# ThermoDisplay.net
KiCad netlist of a schematic drawn in Altium Designer
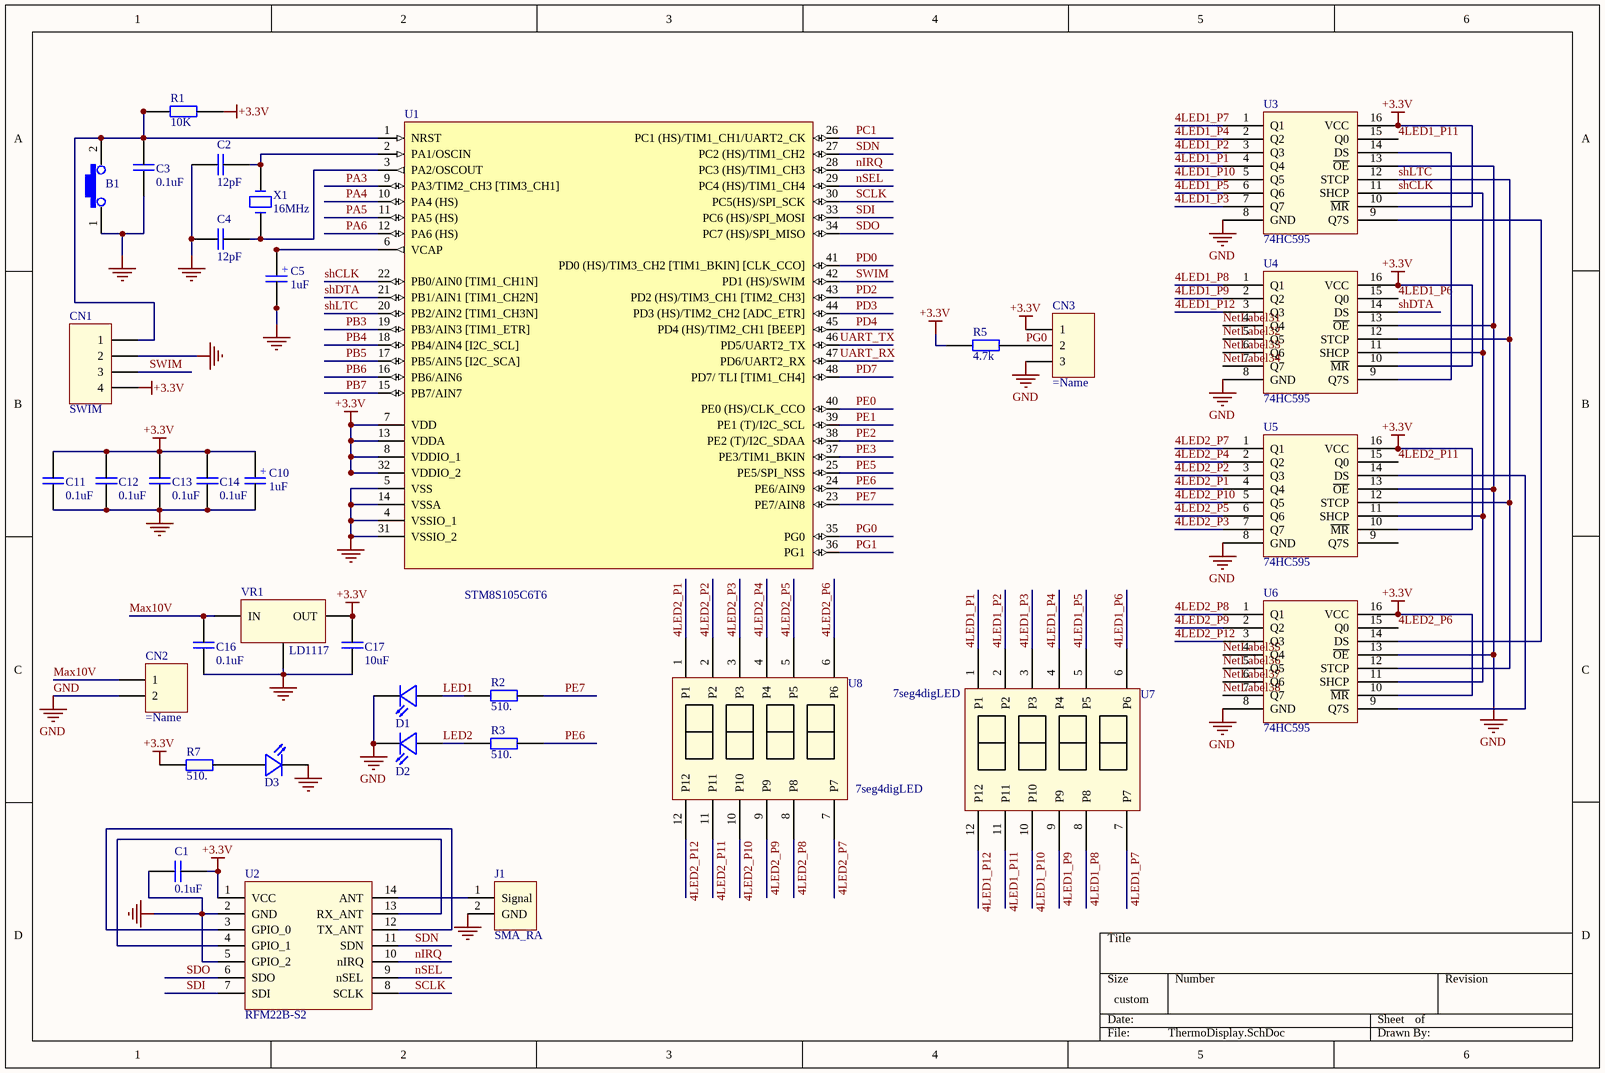
[diagram p0: ThermoDisplay.SchDoc]

(export (version "E")
  (design (tool "Eeschema 10.0.6"))
  (components
    (comp (ref "B1")
      (value "~")
      (footprint "FSMSM")
      (description "Button")
      (fields (field (name "PART NUMBER") "FSM14JRT"))
      (libsource (lib "Library") (part "Button"))
    )
    (comp (ref "C1")
      (value "0.1uF")
      (footprint "Cap0805")
      (description "Capacitor")
      (fields (field (name "PART NUMBER") "Cap 0805 0.1uF") (field (name "TOLERANCE") "±5%"))
      (libsource (lib "Library") (part "Capacitor"))
    )
    (comp (ref "C2")
      (value "12pF")
      (footprint "Cap0805")
      (description "Capacitor")
      (fields (field (name "PART NUMBER") "Cap 0805 12pF") (field (name "TOLERANCE") "±5%"))
      (libsource (lib "Library") (part "Capacitor"))
    )
    (comp (ref "C3")
      (value "0.1uF")
      (footprint "Cap0805")
      (description "Capacitor")
      (fields (field (name "PART NUMBER") "Cap 0805 0.1uF") (field (name "TOLERANCE") "±5%"))
      (libsource (lib "Library") (part "Capacitor"))
    )
    (comp (ref "C4")
      (value "12pF")
      (footprint "Cap0805")
      (description "Capacitor")
      (fields (field (name "PART NUMBER") "Cap 0805 12pF") (field (name "TOLERANCE") "±5%"))
      (libsource (lib "Library") (part "Capacitor"))
    )
    (comp (ref "C5")
      (value "1uF")
      (footprint "TC_A")
      (description "Capacitor polarity")
      (fields (field (name "PART NUMBER") "TCap TC_A 1uF") (field (name "VOLTAGE") "25V"))
      (libsource (lib "Library") (part "Capacitor polarity"))
    )
    (comp (ref "C10")
      (value "1uF")
      (footprint "TC_A")
      (description "Capacitor polarity")
      (fields (field (name "PART NUMBER") "TCap TC_A 1uF") (field (name "VOLTAGE") "25V"))
      (libsource (lib "Library") (part "Capacitor polarity"))
    )
    (comp (ref "C11")
      (value "0.1uF")
      (footprint "Cap0805")
      (description "Capacitor")
      (fields (field (name "PART NUMBER") "Cap 0805 0.1uF") (field (name "TOLERANCE") "±5%"))
      (libsource (lib "Library") (part "Capacitor"))
    )
    (comp (ref "C12")
      (value "0.1uF")
      (footprint "Cap0805")
      (description "Capacitor")
      (fields (field (name "PART NUMBER") "Cap 0805 0.1uF") (field (name "TOLERANCE") "±5%"))
      (libsource (lib "Library") (part "Capacitor"))
    )
    (comp (ref "C13")
      (value "0.1uF")
      (footprint "Cap0805")
      (description "Capacitor")
      (fields (field (name "PART NUMBER") "Cap 0805 0.1uF") (field (name "TOLERANCE") "±5%"))
      (libsource (lib "Library") (part "Capacitor"))
    )
    (comp (ref "C14")
      (value "0.1uF")
      (footprint "Cap0805")
      (description "Capacitor")
      (fields (field (name "PART NUMBER") "Cap 0805 0.1uF") (field (name "TOLERANCE") "±5%"))
      (libsource (lib "Library") (part "Capacitor"))
    )
    (comp (ref "C16")
      (value "0.1uF")
      (footprint "Cap0805")
      (description "Capacitor")
      (fields (field (name "PART NUMBER") "Cap 0805 0.1uF") (field (name "TOLERANCE") "±5%"))
      (libsource (lib "Library") (part "Capacitor"))
    )
    (comp (ref "C17")
      (value "10uF")
      (footprint "Cap0805")
      (description "Capacitor")
      (fields (field (name "PART NUMBER") "Cap 0805 10uF") (field (name "TOLERANCE") "±10%"))
      (libsource (lib "Library") (part "Capacitor"))
    )
    (comp (ref "CN1")
      (value "SWIM")
      (footprint "PLS-4 - bottom")
      (description "PLS-4")
      (libsource (lib "Library") (part "PLS-4"))
    )
    (comp (ref "CN2")
      (value "~")
      (footprint "PLS-2")
      (description "PLS-2")
      (libsource (lib "Library") (part "PLS-2"))
    )
    (comp (ref "CN3")
      (value "~")
      (footprint "PLS-3")
      (description "PLS-3")
      (libsource (lib "Library") (part "PLS-3"))
    )
    (comp (ref "D1")
      (value "Green")
      (footprint "FYLS-0805")
      (description "LED")
      (fields (field (name "PART NUMBER") "FYLS-0805UGC"))
      (libsource (lib "Library") (part "LED"))
    )
    (comp (ref "D2")
      (value "Yellow")
      (footprint "FYLS-0805")
      (description "LED")
      (fields (field (name "PART NUMBER") "FYLS-0805UYC"))
      (libsource (lib "Library") (part "LED"))
    )
    (comp (ref "D3")
      (value "Red")
      (footprint "FYLS-0805")
      (description "LED")
      (fields (field (name "PART NUMBER") "FYLS-0805URC"))
      (libsource (lib "Library") (part "LED"))
    )
    (comp (ref "J1")
      (value "SMA_RA")
      (footprint "SMA_RA")
      (fields (field (name "PART NUMBER") "SMA RIGHT ANGEL PCB"))
      (libsource (lib "Library") (part "SMA_RA"))
    )
    (comp (ref "R1")
      (value "10K")
      (footprint "Res0805")
      (description "Resistor")
      (fields (field (name "PART NUMBER") "Res 0805 10K") (field (name "TOLERANCE") "± 1%"))
      (libsource (lib "Library") (part "Resistor"))
    )
    (comp (ref "R2")
      (value "510.")
      (footprint "Res0805")
      (description "Resistor")
      (fields (field (name "PART NUMBER") "Res 0805 510") (field (name "TOLERANCE") "± 5%"))
      (libsource (lib "Library") (part "Resistor"))
    )
    (comp (ref "R3")
      (value "510.")
      (footprint "Res0805")
      (description "Resistor")
      (fields (field (name "PART NUMBER") "Res 0805 510") (field (name "TOLERANCE") "± 5%"))
      (libsource (lib "Library") (part "Resistor"))
    )
    (comp (ref "R5")
      (value "4.7k")
      (footprint "RES0805")
      (description "Resistor")
      (libsource (lib "Discrete") (part "Resistor"))
    )
    (comp (ref "R7")
      (value "510.")
      (footprint "Res0805")
      (description "Resistor")
      (fields (field (name "PART NUMBER") "Res 0805 510") (field (name "TOLERANCE") "± 5%"))
      (libsource (lib "Library") (part "Resistor"))
    )
    (comp (ref "U1")
      (value "STM8S105C6T6")
      (footprint "LQFP48_H")
      (description "Microcontroller")
      (libsource (lib "Library") (part "STM8S105C6T6"))
    )
    (comp (ref "U2")
      (value "RFM22B-S2")
      (footprint "RFM22B-S2")
      (description "Transmitter")
      (libsource (lib "Library") (part "RFM22B"))
    )
    (comp (ref "U3")
      (value "74HC595")
      (footprint "SO-16_M")
      (description "Shift Register")
      (libsource (lib "ICs") (part "74HC595"))
    )
    (comp (ref "U4")
      (value "74HC595")
      (footprint "SO-16_M")
      (description "Shift Register")
      (libsource (lib "ICs") (part "74HC595"))
    )
    (comp (ref "U5")
      (value "74HC595")
      (footprint "SO-16_M")
      (description "Shift Register")
      (libsource (lib "ICs") (part "74HC595"))
    )
    (comp (ref "U6")
      (value "74HC595")
      (footprint "SO-16_M")
      (description "Shift Register")
      (libsource (lib "ICs") (part "74HC595"))
    )
    (comp (ref "U7")
      (value "7seg4digLED")
      (footprint "LD3361BS")
      (description "7 segment 4-digit LED")
      (libsource (lib "Miscellaneous") (part "7SEG4LED"))
    )
    (comp (ref "U8")
      (value "7seg4digLED")
      (footprint "LD3361BS")
      (description "7 segment 4-digit LED")
      (libsource (lib "Miscellaneous") (part "7SEG4LED"))
    )
    (comp (ref "VR1")
      (value "LD1117")
      (footprint "SOT223_M")
      (description "Voltage Regulator")
      (libsource (lib "Library") (part "LD1117"))
    )
    (comp (ref "X1")
      (value "16MHz")
      (footprint "KX-7")
      (description "XTAL")
      (fields (field (name "PART NUMBER") "KX-7T 16.0 MHz"))
      (libsource (lib "Library") (part "XTAL"))
    )
  )
  (nets
    (net (code "1") (name "+3.3V") (class "Default")
      (node (ref "C1") (pin "2") (pinfunction "2_2") (pintype "passive"))
      (node (ref "C10") (pin "1") (pinfunction "1_1") (pintype "passive"))
      (node (ref "C11") (pin "2") (pinfunction "2_2") (pintype "passive"))
      (node (ref "C12") (pin "2") (pinfunction "2_2") (pintype "passive"))
      (node (ref "C13") (pin "2") (pinfunction "2_2") (pintype "passive"))
      (node (ref "C14") (pin "2") (pinfunction "2_2") (pintype "passive"))
      (node (ref "C17") (pin "2") (pinfunction "2_2") (pintype "passive"))
      (node (ref "CN1") (pin "4") (pinfunction "4_4") (pintype "passive"))
      (node (ref "CN3") (pin "1") (pinfunction "1_1") (pintype "passive"))
      (node (ref "R1") (pin "2") (pinfunction "2_2") (pintype "passive"))
      (node (ref "R5") (pin "1") (pinfunction "1_1") (pintype "passive"))
      (node (ref "R7") (pin "1") (pinfunction "1_1") (pintype "passive"))
      (node (ref "U1") (pin "13") (pinfunction "VDDA_13") (pintype "passive"))
      (node (ref "U1") (pin "32") (pinfunction "VDDIO_2_32") (pintype "passive"))
      (node (ref "U1") (pin "7") (pinfunction "VDD_7") (pintype "passive"))
      (node (ref "U1") (pin "8") (pinfunction "VDDIO_1_8") (pintype "passive"))
      (node (ref "U2") (pin "1") (pinfunction "VCC_1") (pintype "passive"))
      (node (ref "U3") (pin "10") (pinfunction "~{MR}_10") (pintype "passive"))
      (node (ref "U3") (pin "16") (pinfunction "VCC_16") (pintype "passive"))
      (node (ref "U4") (pin "10") (pinfunction "~{MR}_10") (pintype "passive"))
      (node (ref "U4") (pin "16") (pinfunction "VCC_16") (pintype "passive"))
      (node (ref "U5") (pin "10") (pinfunction "~{MR}_10") (pintype "passive"))
      (node (ref "U5") (pin "16") (pinfunction "VCC_16") (pintype "passive"))
      (node (ref "U6") (pin "10") (pinfunction "~{MR}_10") (pintype "passive"))
      (node (ref "U6") (pin "16") (pinfunction "VCC_16") (pintype "passive"))
      (node (ref "VR1") (pin "3") (pinfunction "OUT_3") (pintype "passive"))
    )
    (net (code "2") (name "/4LED1_P1") (class "Default")
      (node (ref "U3") (pin "4") (pinfunction "Q4_4") (pintype "passive"))
      (node (ref "U7") (pin "1") (pinfunction "P1_1") (pintype "passive"))
    )
    (net (code "3") (name "/4LED1_P2") (class "Default")
      (node (ref "U3") (pin "3") (pinfunction "Q3_3") (pintype "passive"))
      (node (ref "U7") (pin "2") (pinfunction "P2_2") (pintype "passive"))
    )
    (net (code "4") (name "/4LED1_P3") (class "Default")
      (node (ref "U3") (pin "7") (pinfunction "Q7_7") (pintype "passive"))
      (node (ref "U7") (pin "3") (pinfunction "P3_3") (pintype "passive"))
    )
    (net (code "5") (name "/4LED1_P4") (class "Default")
      (node (ref "U3") (pin "2") (pinfunction "Q2_2") (pintype "passive"))
      (node (ref "U7") (pin "4") (pinfunction "P4_4") (pintype "passive"))
    )
    (net (code "6") (name "/4LED1_P5") (class "Default")
      (node (ref "U3") (pin "6") (pinfunction "Q6_6") (pintype "passive"))
      (node (ref "U7") (pin "5") (pinfunction "P5_5") (pintype "passive"))
    )
    (net (code "7") (name "/4LED1_P6") (class "Default")
      (node (ref "U4") (pin "15") (pinfunction "Q0_15") (pintype "passive"))
      (node (ref "U7") (pin "6") (pinfunction "P6_6") (pintype "passive"))
    )
    (net (code "8") (name "/4LED1_P7") (class "Default")
      (node (ref "U3") (pin "1") (pinfunction "Q1_1") (pintype "passive"))
      (node (ref "U7") (pin "7") (pinfunction "P7_7") (pintype "passive"))
    )
    (net (code "9") (name "/4LED1_P8") (class "Default")
      (node (ref "U4") (pin "1") (pinfunction "Q1_1") (pintype "passive"))
      (node (ref "U7") (pin "8") (pinfunction "P8_8") (pintype "passive"))
    )
    (net (code "10") (name "/4LED1_P9") (class "Default")
      (node (ref "U4") (pin "2") (pinfunction "Q2_2") (pintype "passive"))
      (node (ref "U7") (pin "9") (pinfunction "P9_9") (pintype "passive"))
    )
    (net (code "11") (name "/4LED1_P10") (class "Default")
      (node (ref "U3") (pin "5") (pinfunction "Q5_5") (pintype "passive"))
      (node (ref "U7") (pin "10") (pinfunction "P10_10") (pintype "passive"))
    )
    (net (code "12") (name "/4LED1_P11") (class "Default")
      (node (ref "U3") (pin "15") (pinfunction "Q0_15") (pintype "passive"))
      (node (ref "U7") (pin "11") (pinfunction "P11_11") (pintype "passive"))
    )
    (net (code "13") (name "/4LED1_P12") (class "Default")
      (node (ref "U4") (pin "3") (pinfunction "Q3_3") (pintype "passive"))
      (node (ref "U7") (pin "12") (pinfunction "P12_12") (pintype "passive"))
    )
    (net (code "14") (name "/4LED2_P1") (class "Default")
      (node (ref "U5") (pin "4") (pinfunction "Q4_4") (pintype "passive"))
      (node (ref "U8") (pin "1") (pinfunction "P1_1") (pintype "passive"))
    )
    (net (code "15") (name "/4LED2_P2") (class "Default")
      (node (ref "U5") (pin "3") (pinfunction "Q3_3") (pintype "passive"))
      (node (ref "U8") (pin "2") (pinfunction "P2_2") (pintype "passive"))
    )
    (net (code "16") (name "/4LED2_P3") (class "Default")
      (node (ref "U5") (pin "7") (pinfunction "Q7_7") (pintype "passive"))
      (node (ref "U8") (pin "3") (pinfunction "P3_3") (pintype "passive"))
    )
    (net (code "17") (name "/4LED2_P4") (class "Default")
      (node (ref "U5") (pin "2") (pinfunction "Q2_2") (pintype "passive"))
      (node (ref "U8") (pin "4") (pinfunction "P4_4") (pintype "passive"))
    )
    (net (code "18") (name "/4LED2_P5") (class "Default")
      (node (ref "U5") (pin "6") (pinfunction "Q6_6") (pintype "passive"))
      (node (ref "U8") (pin "5") (pinfunction "P5_5") (pintype "passive"))
    )
    (net (code "19") (name "/4LED2_P6") (class "Default")
      (node (ref "U6") (pin "15") (pinfunction "Q0_15") (pintype "passive"))
      (node (ref "U8") (pin "6") (pinfunction "P6_6") (pintype "passive"))
    )
    (net (code "20") (name "/4LED2_P7") (class "Default")
      (node (ref "U5") (pin "1") (pinfunction "Q1_1") (pintype "passive"))
      (node (ref "U8") (pin "7") (pinfunction "P7_7") (pintype "passive"))
    )
    (net (code "21") (name "/4LED2_P8") (class "Default")
      (node (ref "U6") (pin "1") (pinfunction "Q1_1") (pintype "passive"))
      (node (ref "U8") (pin "8") (pinfunction "P8_8") (pintype "passive"))
    )
    (net (code "22") (name "/4LED2_P9") (class "Default")
      (node (ref "U6") (pin "2") (pinfunction "Q2_2") (pintype "passive"))
      (node (ref "U8") (pin "9") (pinfunction "P9_9") (pintype "passive"))
    )
    (net (code "23") (name "/4LED2_P10") (class "Default")
      (node (ref "U5") (pin "5") (pinfunction "Q5_5") (pintype "passive"))
      (node (ref "U8") (pin "10") (pinfunction "P10_10") (pintype "passive"))
    )
    (net (code "24") (name "/4LED2_P11") (class "Default")
      (node (ref "U5") (pin "15") (pinfunction "Q0_15") (pintype "passive"))
      (node (ref "U8") (pin "11") (pinfunction "P11_11") (pintype "passive"))
    )
    (net (code "25") (name "/4LED2_P12") (class "Default")
      (node (ref "U6") (pin "3") (pinfunction "Q3_3") (pintype "passive"))
      (node (ref "U8") (pin "12") (pinfunction "P12_12") (pintype "passive"))
    )
    (net (code "26") (name "/LED1") (class "Default")
      (node (ref "D1") (pin "1") (pinfunction "1_1") (pintype "passive"))
      (node (ref "R2") (pin "1") (pinfunction "1_1") (pintype "passive"))
    )
    (net (code "27") (name "/LED2") (class "Default")
      (node (ref "D2") (pin "1") (pinfunction "1_1") (pintype "passive"))
      (node (ref "R3") (pin "1") (pinfunction "1_1") (pintype "passive"))
    )
    (net (code "28") (name "/Max10V") (class "Default")
      (node (ref "C16") (pin "2") (pinfunction "2_2") (pintype "passive"))
      (node (ref "CN2") (pin "1") (pinfunction "1_1") (pintype "passive"))
      (node (ref "VR1") (pin "1") (pinfunction "IN_1") (pintype "passive"))
    )
    (net (code "29") (name "/NetLabel31") (class "Default")
      (node (ref "U4") (pin "4") (pinfunction "Q4_4") (pintype "passive"))
    )
    (net (code "30") (name "/NetLabel32") (class "Default")
      (node (ref "U4") (pin "5") (pinfunction "Q5_5") (pintype "passive"))
    )
    (net (code "31") (name "/NetLabel33") (class "Default")
      (node (ref "U4") (pin "6") (pinfunction "Q6_6") (pintype "passive"))
    )
    (net (code "32") (name "/NetLabel34") (class "Default")
      (node (ref "U4") (pin "7") (pinfunction "Q7_7") (pintype "passive"))
    )
    (net (code "33") (name "/NetLabel35") (class "Default")
      (node (ref "U6") (pin "4") (pinfunction "Q4_4") (pintype "passive"))
    )
    (net (code "34") (name "/NetLabel36") (class "Default")
      (node (ref "U6") (pin "5") (pinfunction "Q5_5") (pintype "passive"))
    )
    (net (code "35") (name "/NetLabel37") (class "Default")
      (node (ref "U6") (pin "6") (pinfunction "Q6_6") (pintype "passive"))
    )
    (net (code "36") (name "/NetLabel38") (class "Default")
      (node (ref "U6") (pin "7") (pinfunction "Q7_7") (pintype "passive"))
    )
    (net (code "37") (name "/PA3") (class "Default")
      (node (ref "U1") (pin "9") (pinfunction "PA3/TIM2_CH3_[TIM3_CH1]_9") (pintype "bidirectional"))
    )
    (net (code "38") (name "/PA4") (class "Default")
      (node (ref "U1") (pin "10") (pinfunction "PA4_(HS)_10") (pintype "bidirectional"))
    )
    (net (code "39") (name "/PA5") (class "Default")
      (node (ref "U1") (pin "11") (pinfunction "PA5_(HS)_11") (pintype "bidirectional"))
    )
    (net (code "40") (name "/PA6") (class "Default")
      (node (ref "U1") (pin "12") (pinfunction "PA6_(HS)_12") (pintype "bidirectional"))
    )
    (net (code "41") (name "/PB3") (class "Default")
      (node (ref "U1") (pin "19") (pinfunction "PB3/AIN3_[TIM1_ETR]_19") (pintype "bidirectional"))
    )
    (net (code "42") (name "/PB4") (class "Default")
      (node (ref "U1") (pin "18") (pinfunction "PB4/AIN4_[I2C_SCL]_18") (pintype "bidirectional"))
    )
    (net (code "43") (name "/PB5") (class "Default")
      (node (ref "U1") (pin "17") (pinfunction "PB5/AIN5_[I2C_SCA]_17") (pintype "bidirectional"))
    )
    (net (code "44") (name "/PB6") (class "Default")
      (node (ref "U1") (pin "16") (pinfunction "PB6/AIN6_16") (pintype "bidirectional"))
    )
    (net (code "45") (name "/PB7") (class "Default")
      (node (ref "U1") (pin "15") (pinfunction "PB7/AIN7_15") (pintype "bidirectional"))
    )
    (net (code "46") (name "/PC1") (class "Default")
      (node (ref "U1") (pin "26") (pinfunction "PC1_(HS)/TIM1_CH1/UART2_CK_26") (pintype "bidirectional"))
    )
    (net (code "47") (name "/PD0") (class "Default")
      (node (ref "U1") (pin "41") (pinfunction "PD0_(HS)/TIM3_CH2_[TIM1_BKIN]_[CLK_CCO]_41") (pintype "bidirectional"))
    )
    (net (code "48") (name "/PD2") (class "Default")
      (node (ref "U1") (pin "43") (pinfunction "PD2_(HS)/TIM3_CH1_[TIM2_CH3]_43") (pintype "bidirectional"))
    )
    (net (code "49") (name "/PD3") (class "Default")
      (node (ref "U1") (pin "44") (pinfunction "PD3_(HS)/TIM2_CH2_[ADC_ETR]_44") (pintype "bidirectional"))
    )
    (net (code "50") (name "/PD4") (class "Default")
      (node (ref "U1") (pin "45") (pinfunction "PD4_(HS)/TIM2_CH1_[BEEP]_45") (pintype "bidirectional"))
    )
    (net (code "51") (name "/PD7") (class "Default")
      (node (ref "U1") (pin "48") (pinfunction "PD7/_TLI_[TIM1_CH4]_48") (pintype "bidirectional"))
    )
    (net (code "52") (name "/PE0") (class "Default")
      (node (ref "U1") (pin "40") (pinfunction "PE0_(HS)/CLK_CCO_40") (pintype "bidirectional"))
    )
    (net (code "53") (name "/PE1") (class "Default")
      (node (ref "U1") (pin "39") (pinfunction "PE1_(T)/I2C_SCL_39") (pintype "bidirectional"))
    )
    (net (code "54") (name "/PE2") (class "Default")
      (node (ref "U1") (pin "38") (pinfunction "PE2_(T)/I2C_SDAA_38") (pintype "bidirectional"))
    )
    (net (code "55") (name "/PE3") (class "Default")
      (node (ref "U1") (pin "37") (pinfunction "PE3/TIM1_BKIN_37") (pintype "bidirectional"))
    )
    (net (code "56") (name "/PE5") (class "Default")
      (node (ref "U1") (pin "25") (pinfunction "PE5/SPI_NSS_25") (pintype "bidirectional"))
    )
    (net (code "57") (name "/PE6") (class "Default")
      (node (ref "R3") (pin "2") (pinfunction "2_2") (pintype "passive"))
      (node (ref "U1") (pin "24") (pinfunction "PE6/AIN9_24") (pintype "bidirectional"))
    )
    (net (code "58") (name "/PE7") (class "Default")
      (node (ref "R2") (pin "2") (pinfunction "2_2") (pintype "passive"))
      (node (ref "U1") (pin "23") (pinfunction "PE7/AIN8_23") (pintype "bidirectional"))
    )
    (net (code "59") (name "/PG0") (class "Default")
      (node (ref "CN3") (pin "2") (pinfunction "2_2") (pintype "passive"))
      (node (ref "R5") (pin "2") (pinfunction "2_2") (pintype "passive"))
      (node (ref "U1") (pin "35") (pinfunction "PG0_35") (pintype "bidirectional"))
    )
    (net (code "60") (name "/PG1") (class "Default")
      (node (ref "U1") (pin "36") (pinfunction "PG1_36") (pintype "bidirectional"))
    )
    (net (code "61") (name "/SCLK") (class "Default")
      (node (ref "U1") (pin "30") (pinfunction "PC5(HS)/SPI_SCK_30") (pintype "bidirectional"))
      (node (ref "U2") (pin "8") (pinfunction "SCLK_8") (pintype "passive"))
    )
    (net (code "62") (name "/SDI") (class "Default")
      (node (ref "U1") (pin "33") (pinfunction "PC6_(HS)/SPI_MOSI_33") (pintype "bidirectional"))
      (node (ref "U2") (pin "7") (pinfunction "SDI_7") (pintype "passive"))
    )
    (net (code "63") (name "/SDN") (class "Default")
      (node (ref "U1") (pin "27") (pinfunction "PC2_(HS)/TIM1_CH2_27") (pintype "bidirectional"))
      (node (ref "U2") (pin "11") (pinfunction "SDN_11") (pintype "passive"))
    )
    (net (code "64") (name "/SDO") (class "Default")
      (node (ref "U1") (pin "34") (pinfunction "PC7_(HS)/SPI_MISO_34") (pintype "bidirectional"))
      (node (ref "U2") (pin "6") (pinfunction "SDO_6") (pintype "passive"))
    )
    (net (code "65") (name "/SWIM") (class "Default")
      (node (ref "CN1") (pin "3") (pinfunction "3_3") (pintype "passive"))
      (node (ref "U1") (pin "42") (pinfunction "PD1_(HS)/SWIM_42") (pintype "bidirectional"))
    )
    (net (code "66") (name "/UART_RX") (class "Default")
      (node (ref "U1") (pin "47") (pinfunction "PD6/UART2_RX_47") (pintype "bidirectional"))
    )
    (net (code "67") (name "/UART_TX") (class "Default")
      (node (ref "U1") (pin "46") (pinfunction "PD5/UART2_TX_46") (pintype "bidirectional"))
    )
    (net (code "68") (name "/nIRQ") (class "Default")
      (node (ref "U1") (pin "28") (pinfunction "PC3_(HS)/TIM1_CH3_28") (pintype "bidirectional"))
      (node (ref "U2") (pin "10") (pinfunction "nIRQ_10") (pintype "passive"))
    )
    (net (code "69") (name "/nSEL") (class "Default")
      (node (ref "U1") (pin "29") (pinfunction "PC4_(HS)/TIM1_CH4_29") (pintype "bidirectional"))
      (node (ref "U2") (pin "9") (pinfunction "nSEL_9") (pintype "passive"))
    )
    (net (code "70") (name "/shCLK") (class "Default")
      (node (ref "U1") (pin "22") (pinfunction "PB0/AIN0_[TIM1_CH1N]_22") (pintype "bidirectional"))
      (node (ref "U3") (pin "11") (pinfunction "SHCP_11") (pintype "passive"))
      (node (ref "U4") (pin "11") (pinfunction "SHCP_11") (pintype "passive"))
      (node (ref "U5") (pin "11") (pinfunction "SHCP_11") (pintype "passive"))
      (node (ref "U6") (pin "11") (pinfunction "SHCP_11") (pintype "passive"))
    )
    (net (code "71") (name "/shDTA") (class "Default")
      (node (ref "U1") (pin "21") (pinfunction "PB1/AIN1_[TIM1_CH2N]_21") (pintype "bidirectional"))
      (node (ref "U4") (pin "14") (pinfunction "DS_14") (pintype "passive"))
    )
    (net (code "72") (name "/shLTC") (class "Default")
      (node (ref "U1") (pin "20") (pinfunction "PB2/AIN2_[TIM1_CH3N]_20") (pintype "bidirectional"))
      (node (ref "U3") (pin "12") (pinfunction "STCP_12") (pintype "passive"))
      (node (ref "U4") (pin "12") (pinfunction "STCP_12") (pintype "passive"))
      (node (ref "U5") (pin "12") (pinfunction "STCP_12") (pintype "passive"))
      (node (ref "U6") (pin "12") (pinfunction "STCP_12") (pintype "passive"))
    )
    (net (code "73") (name "GND") (class "Default")
      (node (ref "B1") (pin "1") (pinfunction "1_1") (pintype "passive"))
      (node (ref "C1") (pin "1") (pinfunction "1_1") (pintype "passive"))
      (node (ref "C10") (pin "2") (pinfunction "2_2") (pintype "passive"))
      (node (ref "C11") (pin "1") (pinfunction "1_1") (pintype "passive"))
      (node (ref "C12") (pin "1") (pinfunction "1_1") (pintype "passive"))
      (node (ref "C13") (pin "1") (pinfunction "1_1") (pintype "passive"))
      (node (ref "C14") (pin "1") (pinfunction "1_1") (pintype "passive"))
      (node (ref "C16") (pin "1") (pinfunction "1_1") (pintype "passive"))
      (node (ref "C17") (pin "1") (pinfunction "1_1") (pintype "passive"))
      (node (ref "C2") (pin "1") (pinfunction "1_1") (pintype "passive"))
      (node (ref "C3") (pin "1") (pinfunction "1_1") (pintype "passive"))
      (node (ref "C4") (pin "1") (pinfunction "1_1") (pintype "passive"))
      (node (ref "C5") (pin "2") (pinfunction "2_2") (pintype "passive"))
      (node (ref "CN1") (pin "2") (pinfunction "2_2") (pintype "passive"))
      (node (ref "CN2") (pin "2") (pinfunction "2_2") (pintype "passive"))
      (node (ref "CN3") (pin "3") (pinfunction "3_3") (pintype "passive"))
      (node (ref "D1") (pin "2") (pinfunction "2_2") (pintype "passive"))
      (node (ref "D2") (pin "2") (pinfunction "2_2") (pintype "passive"))
      (node (ref "D3") (pin "2") (pinfunction "2_2") (pintype "passive"))
      (node (ref "J1") (pin "2") (pinfunction "GND_2") (pintype "passive"))
      (node (ref "U1") (pin "14") (pinfunction "VSSA_14") (pintype "passive"))
      (node (ref "U1") (pin "31") (pinfunction "VSSIO_2_31") (pintype "passive"))
      (node (ref "U1") (pin "4") (pinfunction "VSSIO_1_4") (pintype "passive"))
      (node (ref "U1") (pin "5") (pinfunction "VSS_5") (pintype "passive"))
      (node (ref "U2") (pin "2") (pinfunction "GND_2") (pintype "passive"))
      (node (ref "U2") (pin "5") (pinfunction "GPIO_2_5") (pintype "passive"))
      (node (ref "U3") (pin "13") (pinfunction "~{OE}_13") (pintype "passive"))
      (node (ref "U3") (pin "8") (pinfunction "GND_8") (pintype "passive"))
      (node (ref "U4") (pin "13") (pinfunction "~{OE}_13") (pintype "passive"))
      (node (ref "U4") (pin "8") (pinfunction "GND_8") (pintype "passive"))
      (node (ref "U5") (pin "13") (pinfunction "~{OE}_13") (pintype "passive"))
      (node (ref "U5") (pin "8") (pinfunction "GND_8") (pintype "passive"))
      (node (ref "U6") (pin "13") (pinfunction "~{OE}_13") (pintype "passive"))
      (node (ref "U6") (pin "8") (pinfunction "GND_8") (pintype "passive"))
      (node (ref "VR1") (pin "2") (pinfunction "GND_2") (pintype "passive"))
    )
    (net (code "74") (name "Net-(D3-Pad1)") (class "Default")
      (node (ref "D3") (pin "1") (pinfunction "1_1") (pintype "passive"))
      (node (ref "R7") (pin "2") (pinfunction "2_2") (pintype "passive"))
    )
    (net (code "75") (name "Net-(J1-Signal)") (class "Default")
      (node (ref "J1") (pin "1") (pinfunction "Signal_1") (pintype "passive"))
      (node (ref "U2") (pin "14") (pinfunction "ANT_14") (pintype "passive"))
    )
    (net (code "76") (name "Net-(U1-NRST)") (class "Default")
      (node (ref "B1") (pin "2") (pinfunction "2_2") (pintype "passive"))
      (node (ref "C3") (pin "2") (pinfunction "2_2") (pintype "passive"))
      (node (ref "CN1") (pin "1") (pinfunction "1_1") (pintype "passive"))
      (node (ref "R1") (pin "1") (pinfunction "1_1") (pintype "passive"))
      (node (ref "U1") (pin "1") (pinfunction "NRST_1") (pintype "input"))
    )
    (net (code "77") (name "Net-(U1-PA1{slash}OSCIN)") (class "Default")
      (node (ref "C2") (pin "2") (pinfunction "2_2") (pintype "passive"))
      (node (ref "U1") (pin "2") (pinfunction "PA1/OSCIN_2") (pintype "input"))
      (node (ref "X1") (pin "2") (pinfunction "2_2") (pintype "passive"))
    )
    (net (code "78") (name "Net-(U1-PA2{slash}OSCOUT)") (class "Default")
      (node (ref "C4") (pin "2") (pinfunction "2_2") (pintype "passive"))
      (node (ref "U1") (pin "3") (pinfunction "PA2/OSCOUT_3") (pintype "output"))
      (node (ref "X1") (pin "1") (pinfunction "1_1") (pintype "passive"))
    )
    (net (code "79") (name "Net-(U1-VCAP)") (class "Default")
      (node (ref "C5") (pin "1") (pinfunction "1_1") (pintype "passive"))
      (node (ref "U1") (pin "6") (pinfunction "VCAP_6") (pintype "output"))
    )
    (net (code "80") (name "Net-(U2-GPIO_0)") (class "Default")
      (node (ref "U2") (pin "12") (pinfunction "TX_ANT_12") (pintype "passive"))
      (node (ref "U2") (pin "3") (pinfunction "GPIO_0_3") (pintype "passive"))
    )
    (net (code "81") (name "Net-(U2-GPIO_1)") (class "Default")
      (node (ref "U2") (pin "13") (pinfunction "RX_ANT_13") (pintype "passive"))
      (node (ref "U2") (pin "4") (pinfunction "GPIO_1_4") (pintype "passive"))
    )
    (net (code "82") (name "Net-(U3-DS)") (class "Default")
      (node (ref "U3") (pin "14") (pinfunction "DS_14") (pintype "passive"))
      (node (ref "U4") (pin "9") (pinfunction "Q7S_9") (pintype "passive"))
    )
    (net (code "83") (name "Net-(U3-Q7S)") (class "Default")
      (node (ref "U3") (pin "9") (pinfunction "Q7S_9") (pintype "passive"))
      (node (ref "U6") (pin "14") (pinfunction "DS_14") (pintype "passive"))
    )
    (net (code "84") (name "Net-(U5-DS)") (class "Default")
      (node (ref "U5") (pin "14") (pinfunction "DS_14") (pintype "passive"))
      (node (ref "U6") (pin "9") (pinfunction "Q7S_9") (pintype "passive"))
    )
    (net (code "85") (name "unconnected-(U5-Q7S-Pad9)") (class "Default")
      (node (ref "U5") (pin "9") (pinfunction "Q7S_9") (pintype "passive"))
    )
  )
)
